# 1_zasilanie.net
KiCad netlist of a schematic drawn in Altium Designer
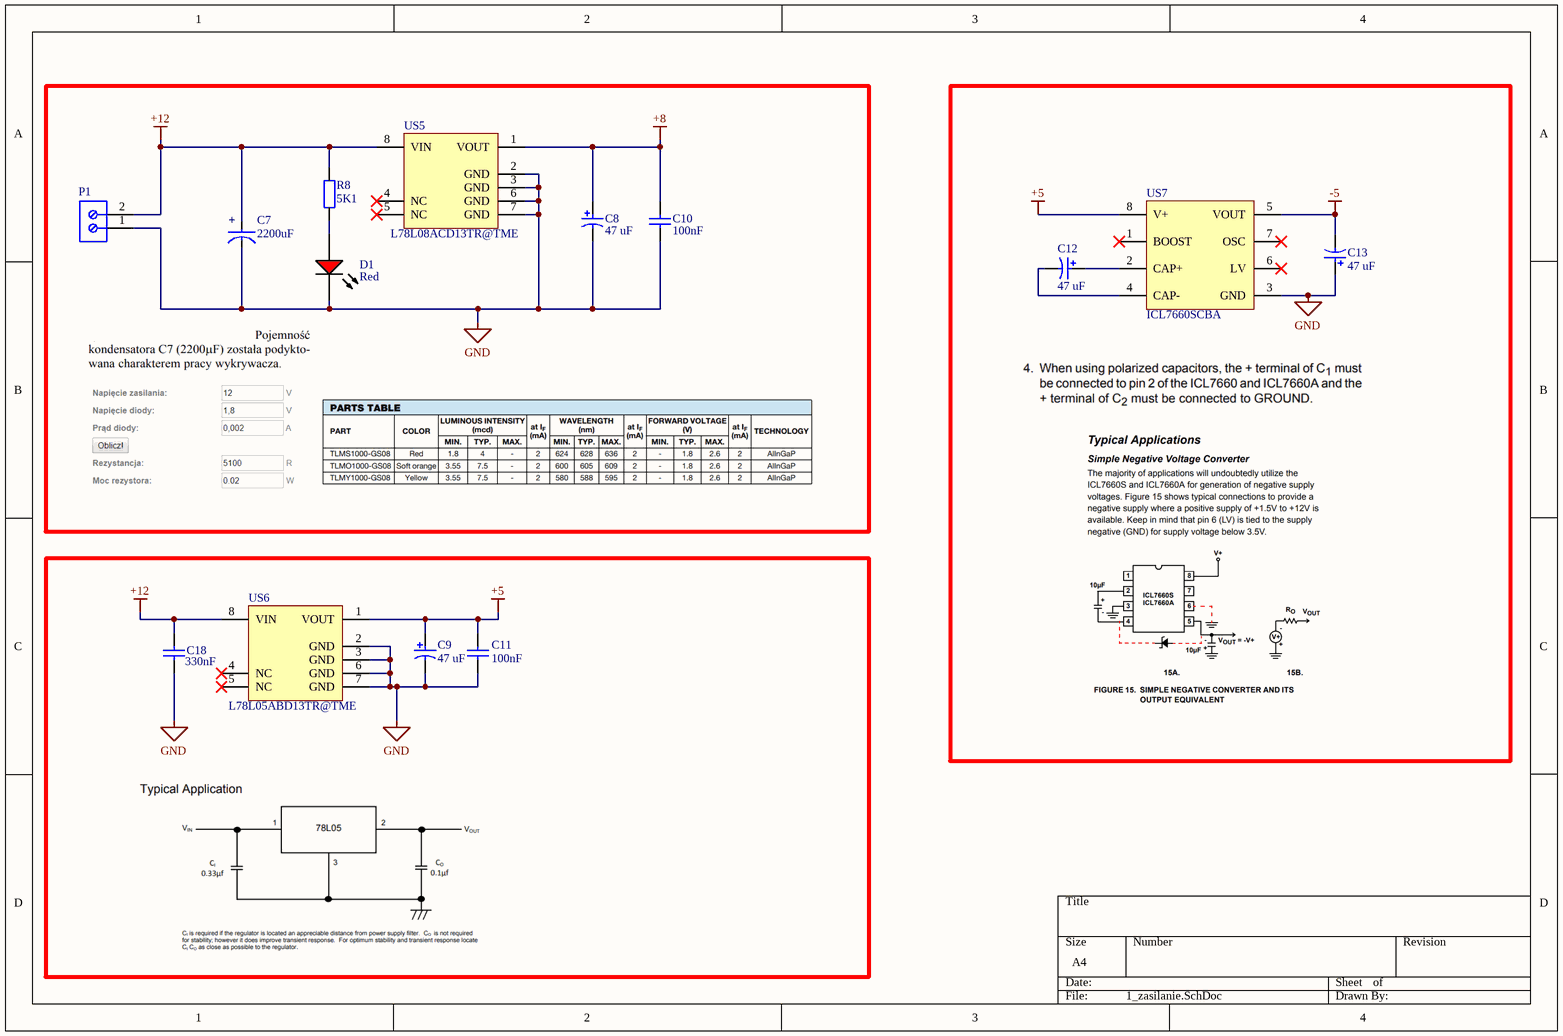
[diagram p0: 1_zasilanie.SchDoc]

(export (version "E")
  (design (tool "Eeschema 10.0.6"))
  (components
    (comp (ref "C7")
      (value "Cap Electrolytic")
      (footprint "Capacitors_MT_Library:18 X 25mm Radial 7.5mm")
      (description "CAPACITOR ALUM 2200UF 20% 35V RADIAL")
      (fields (field (name "CAPACITANCE") "2200uF"))
      (libsource (lib "MT_Library") (part "Cap Electrolytic"))
    )
    (comp (ref "C8")
      (value "UUD1E470MCL1GS")
      (footprint "NIC-CAPA2-6.3X5.8_V")
      (fields (field (name "MANUFACTURER") "Nichicon") (field (name "RATED CAPACITANCE") "47 uF"))
      (libsource (lib "Altium Content Vault") (part "NIC-CAP-P-2"))
    )
    (comp (ref "C9")
      (value "UUD1E470MCL1GS")
      (footprint "NIC-CAPA2-6.3X5.8_V")
      (fields (field (name "MANUFACTURER") "Nichicon") (field (name "RATED CAPACITANCE") "47 uF"))
      (libsource (lib "Altium Content Vault") (part "NIC-CAP-P-2"))
    )
    (comp (ref "C10")
      (value "CL10B104KA8NNNC@TME")
      (footprint "0603")
      (description "Capacitor")
      (fields (field (name "CAPACITANCE") "100nF"))
      (libsource (lib "MT_Library") (part "Cap"))
    )
    (comp (ref "C11")
      (value "CL10B104KA8NNNC@TME")
      (footprint "0603")
      (description "Capacitor")
      (fields (field (name "CAPACITANCE") "100nF"))
      (libsource (lib "MT_Library") (part "Cap"))
    )
    (comp (ref "C12")
      (value "UUD1E470MCL1GS")
      (footprint "NIC-CAPA2-6.3X5.8_V")
      (fields (field (name "MANUFACTURER") "Nichicon") (field (name "RATED CAPACITANCE") "47 uF"))
      (libsource (lib "Altium Content Vault") (part "NIC-CAP-P-2"))
    )
    (comp (ref "C13")
      (value "UUD1E470MCL1GS")
      (footprint "NIC-CAPA2-6.3X5.8_V")
      (fields (field (name "MANUFACTURER") "Nichicon") (field (name "RATED CAPACITANCE") "47 uF"))
      (libsource (lib "Altium Content Vault") (part "NIC-CAP-P-2"))
    )
    (comp (ref "C18")
      (value "330nF")
      (footprint "CAPC1608X90X35ML15T15")
      (fields
        (field (name "PART NUMBER") "0603YD334KAT2A")
        (field (name "MANUFACTURER") "AVX Interconnect / Elco")
      )
      (libsource (lib "Altium Content Vault") (part "CAP"))
    )
    (comp (ref "D1")
      (value "TLMS1000-GS08")
      (footprint "VISH-TLMS1000_V")
      (description "Low Current LED, 40 mW, 1.8 V, -40 to 100 degC, 2-Pin SMD (0603), RoHS, Tape and Reel")
      (fields (field (name "LED COLOUR") "Red") (field (name "MANUFACTURER") "Vishay"))
      (libsource (lib "Altium Content Vault") (part "LED-RED-AK-2"))
    )
    (comp (ref "P1")
      (value "282836-2@TME")
      (footprint "TECO-282836-2_V")
      (description "Female Header, Pitch 5 mm, 1 x 2 Position, Height 10 mm, Tail Length 3.5 mm, Rohs, Bulk")
      (fields (field (name "VOLTAGE") "300V") (field (name "MANUFACTURER") "TE Connectivity"))
      (libsource (lib "Altium Content Vault") (part "CN-1P-F-TB2"))
    )
    (comp (ref "R8")
      (value "5K1")
      (footprint "R1206")
      (description "Resistor")
      (fields (field (name "Comment") "1206S4J0102T5E@TME"))
      (libsource (lib "MT_Library") (part "Res"))
    )
    (comp (ref "US5")
      (value "L78L08ACD13TR@TME")
      (footprint "SO8_M")
      (description "Positive Voltage Regulator, 8V, 8-Pin SO, Tape and Reel")
      (libsource (lib "Altium Content Vault") (part "PM-REG-7805-IL8"))
    )
    (comp (ref "US6")
      (value "L78L05ABD13TR@TME")
      (footprint "SO8_N")
      (description "Positive Voltage Regulator, 5V, 8-Pin SO, Tape and Reel")
      (libsource (lib "Altium Content Vault") (part "PM-REG-7805-IL8"))
    )
    (comp (ref "US7")
      (value "ICL7660SCBA")
      (footprint "INTS-SOIC-8_V")
      (fields (field (name "MANUFACTURER") "Intersil"))
      (libsource (lib "Altium Content Vault") (part "INTS-ICL7660S-8"))
    )
  )
  (nets
    (net (code "1") (name "+5") (class "Default")
      (node (ref "C11") (pin "1") (pinfunction "1_1") (pintype "passive"))
      (node (ref "C9") (pin "1") (pinfunction "1_1") (pintype "passive"))
      (node (ref "US6") (pin "1") (pinfunction "VOUT_1") (pintype "power_in"))
      (node (ref "US7") (pin "8") (pinfunction "V+_8") (pintype "power_in"))
    )
    (net (code "2") (name "+8") (class "Default")
      (node (ref "C10") (pin "1") (pinfunction "1_1") (pintype "passive"))
      (node (ref "C8") (pin "1") (pinfunction "1_1") (pintype "passive"))
      (node (ref "US5") (pin "1") (pinfunction "VOUT_1") (pintype "power_in"))
    )
    (net (code "3") (name "+12") (class "Default")
      (node (ref "C18") (pin "1") (pinfunction "1_1") (pintype "passive"))
      (node (ref "C7") (pin "2") (pinfunction "+_2") (pintype "passive"))
      (node (ref "P1") (pin "2") (pinfunction "-_2") (pintype "power_in"))
      (node (ref "R8") (pin "2") (pinfunction "2_2") (pintype "passive"))
      (node (ref "US5") (pin "8") (pinfunction "VIN_8") (pintype "power_in"))
      (node (ref "US6") (pin "8") (pinfunction "VIN_8") (pintype "power_in"))
    )
    (net (code "4") (name "-5") (class "Default")
      (node (ref "C13") (pin "2") (pinfunction "2_2") (pintype "passive"))
      (node (ref "US7") (pin "5") (pinfunction "VOUT_5") (pintype "power_in"))
    )
    (net (code "5") (name "GND") (class "Default")
      (node (ref "C10") (pin "2") (pinfunction "2_2") (pintype "passive"))
      (node (ref "C11") (pin "2") (pinfunction "2_2") (pintype "passive"))
      (node (ref "C13") (pin "1") (pinfunction "1_1") (pintype "passive"))
      (node (ref "C18") (pin "2") (pinfunction "2_2") (pintype "passive"))
      (node (ref "C7") (pin "1") (pinfunction "-_1") (pintype "passive"))
      (node (ref "C8") (pin "2") (pinfunction "2_2") (pintype "passive"))
      (node (ref "C9") (pin "2") (pinfunction "2_2") (pintype "passive"))
      (node (ref "D1") (pin "2") (pinfunction "K_2") (pintype "passive"))
      (node (ref "P1") (pin "1") (pinfunction "+_1") (pintype "power_in"))
      (node (ref "US5") (pin "2") (pinfunction "GND_2") (pintype "power_in"))
      (node (ref "US5") (pin "3") (pinfunction "GND_3") (pintype "power_in"))
      (node (ref "US5") (pin "6") (pinfunction "GND_6") (pintype "power_in"))
      (node (ref "US5") (pin "7") (pinfunction "GND_7") (pintype "power_in"))
      (node (ref "US6") (pin "2") (pinfunction "GND_2") (pintype "power_in"))
      (node (ref "US6") (pin "3") (pinfunction "GND_3") (pintype "power_in"))
      (node (ref "US6") (pin "6") (pinfunction "GND_6") (pintype "power_in"))
      (node (ref "US6") (pin "7") (pinfunction "GND_7") (pintype "power_in"))
      (node (ref "US7") (pin "3") (pinfunction "GND_3") (pintype "power_in"))
    )
    (net (code "6") (name "Net-(D1-A)") (class "Default")
      (node (ref "D1") (pin "1") (pinfunction "A_1") (pintype "passive"))
      (node (ref "R8") (pin "1") (pinfunction "1_1") (pintype "passive"))
    )
    (net (code "7") (name "Net-(US7-CAP+)") (class "Default")
      (node (ref "C12") (pin "1") (pinfunction "1_1") (pintype "passive"))
      (node (ref "US7") (pin "2") (pinfunction "CAP+_2") (pintype "passive"))
    )
    (net (code "8") (name "Net-(US7-CAP-)") (class "Default")
      (node (ref "C12") (pin "2") (pinfunction "2_2") (pintype "passive"))
      (node (ref "US7") (pin "4") (pinfunction "CAP-_4") (pintype "passive"))
    )
    (net (code "9") (name "unconnected-(US5-NC-Pad4)") (class "Default")
      (node (ref "US5") (pin "4") (pinfunction "NC_4") (pintype "passive+no_connect"))
    )
    (net (code "10") (name "unconnected-(US5-NC-Pad5)") (class "Default")
      (node (ref "US5") (pin "5") (pinfunction "NC_5") (pintype "passive+no_connect"))
    )
    (net (code "11") (name "unconnected-(US6-NC-Pad4)") (class "Default")
      (node (ref "US6") (pin "4") (pinfunction "NC_4") (pintype "passive+no_connect"))
    )
    (net (code "12") (name "unconnected-(US6-NC-Pad5)") (class "Default")
      (node (ref "US6") (pin "5") (pinfunction "NC_5") (pintype "passive+no_connect"))
    )
    (net (code "13") (name "unconnected-(US7-BOOST-Pad1)") (class "Default")
      (node (ref "US7") (pin "1") (pinfunction "BOOST_1") (pintype "passive+no_connect"))
    )
    (net (code "14") (name "unconnected-(US7-LV-Pad6)") (class "Default")
      (node (ref "US7") (pin "6") (pinfunction "LV_6") (pintype "power_in+no_connect"))
    )
    (net (code "15") (name "unconnected-(US7-OSC-Pad7)") (class "Default")
      (node (ref "US7") (pin "7") (pinfunction "OSC_7") (pintype "passive+no_connect"))
    )
  )
)
